# pca10056_sheet3_pin_map.net
KiCad netlist of a schematic drawn in Altium Designer
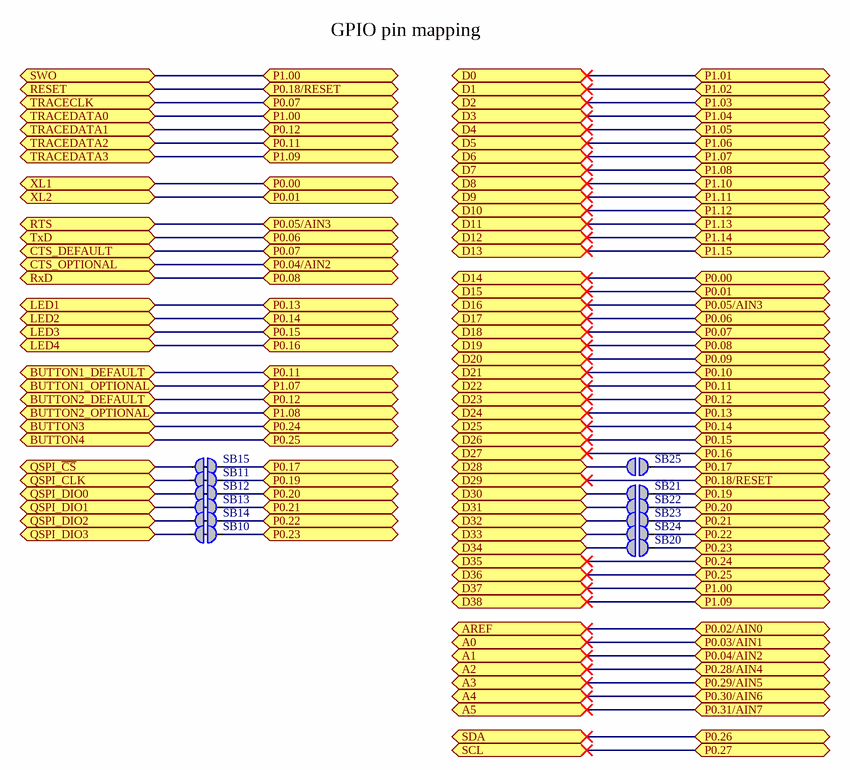
[diagram p0: pca10056_sheet3_pin_map.SchDoc]

(export (version "E")
  (design (tool "Eeschema 10.0.6"))
  (components
    (comp (ref "SB10")
      (value "Solderbridge")
      (footprint "Solderbridge_Shorted")
      (description "Shorted Solderbridge")
      (fields
        (field (name "PART NUMBER") "Solderbridge Shorted")
        (field (name "PUBLISHER") "Nordic Semiconductor")
      )
      (libsource (lib "Nordic Passive DB") (part "SOLDERBRIDGE_SHORTED"))
    )
    (comp (ref "SB11")
      (value "Solderbridge")
      (footprint "Solderbridge_Shorted")
      (description "Shorted Solderbridge")
      (fields
        (field (name "PART NUMBER") "Solderbridge Shorted")
        (field (name "PUBLISHER") "Nordic Semiconductor")
      )
      (libsource (lib "Nordic Passive DB") (part "SOLDERBRIDGE_SHORTED"))
    )
    (comp (ref "SB12")
      (value "Solderbridge")
      (footprint "Solderbridge_Shorted")
      (description "Shorted Solderbridge")
      (fields
        (field (name "PART NUMBER") "Solderbridge Shorted")
        (field (name "PUBLISHER") "Nordic Semiconductor")
      )
      (libsource (lib "Nordic Passive DB") (part "SOLDERBRIDGE_SHORTED"))
    )
    (comp (ref "SB13")
      (value "Solderbridge")
      (footprint "Solderbridge_Shorted")
      (description "Shorted Solderbridge")
      (fields
        (field (name "PART NUMBER") "Solderbridge Shorted")
        (field (name "PUBLISHER") "Nordic Semiconductor")
      )
      (libsource (lib "Nordic Passive DB") (part "SOLDERBRIDGE_SHORTED"))
    )
    (comp (ref "SB14")
      (value "Solderbridge")
      (footprint "Solderbridge_Shorted")
      (description "Shorted Solderbridge")
      (fields
        (field (name "PART NUMBER") "Solderbridge Shorted")
        (field (name "PUBLISHER") "Nordic Semiconductor")
      )
      (libsource (lib "Nordic Passive DB") (part "SOLDERBRIDGE_SHORTED"))
    )
    (comp (ref "SB15")
      (value "Solderbridge")
      (footprint "Solderbridge_Shorted")
      (description "Shorted Solderbridge")
      (fields
        (field (name "PART NUMBER") "Solderbridge Shorted")
        (field (name "PUBLISHER") "Nordic Semiconductor")
      )
      (libsource (lib "Nordic Passive DB") (part "SOLDERBRIDGE_SHORTED"))
    )
    (comp (ref "SB20")
      (value "Solderbridge")
      (footprint "Solderbridge")
      (fields (field (name "PUBLISHER") "Nordic Semiconductor"))
      (libsource (lib "Nordic Passive DB") (part "SOLDERBRIDGE"))
    )
    (comp (ref "SB21")
      (value "Solderbridge")
      (footprint "Solderbridge")
      (fields (field (name "PUBLISHER") "Nordic Semiconductor"))
      (libsource (lib "Nordic Passive DB") (part "SOLDERBRIDGE"))
    )
    (comp (ref "SB22")
      (value "Solderbridge")
      (footprint "Solderbridge")
      (fields (field (name "PUBLISHER") "Nordic Semiconductor"))
      (libsource (lib "Nordic Passive DB") (part "SOLDERBRIDGE"))
    )
    (comp (ref "SB23")
      (value "Solderbridge")
      (footprint "Solderbridge")
      (fields (field (name "PUBLISHER") "Nordic Semiconductor"))
      (libsource (lib "Nordic Passive DB") (part "SOLDERBRIDGE"))
    )
    (comp (ref "SB24")
      (value "Solderbridge")
      (footprint "Solderbridge")
      (fields (field (name "PUBLISHER") "Nordic Semiconductor"))
      (libsource (lib "Nordic Passive DB") (part "SOLDERBRIDGE"))
    )
    (comp (ref "SB25")
      (value "Solderbridge")
      (footprint "Solderbridge")
      (fields (field (name "PUBLISHER") "Nordic Semiconductor"))
      (libsource (lib "Nordic Passive DB") (part "SOLDERBRIDGE"))
    )
  )
  (nets
    (net (code "38") (name "/D28") (class "Default")
      (node (ref "SB25") (pin "2") (pinfunction "1_2") (pintype "passive"))
    )
    (net (code "40") (name "/D30") (class "Default")
      (node (ref "SB21") (pin "2") (pinfunction "1_2") (pintype "passive"))
    )
    (net (code "41") (name "/D31") (class "Default")
      (node (ref "SB22") (pin "2") (pinfunction "1_2") (pintype "passive"))
    )
    (net (code "42") (name "/D32") (class "Default")
      (node (ref "SB23") (pin "2") (pinfunction "1_2") (pintype "passive"))
    )
    (net (code "43") (name "/D33") (class "Default")
      (node (ref "SB24") (pin "2") (pinfunction "1_2") (pintype "passive"))
    )
    (net (code "44") (name "/D34") (class "Default")
      (node (ref "SB20") (pin "2") (pinfunction "1_2") (pintype "passive"))
    )
    (net (code "47") (name "/P0.17") (class "Default")
      (node (ref "SB15") (pin "1") (pinfunction "0_1") (pintype "passive"))
      (node (ref "SB25") (pin "1") (pinfunction "0_1") (pintype "passive"))
    )
    (net (code "48") (name "/P0.19") (class "Default")
      (node (ref "SB11") (pin "1") (pinfunction "0_1") (pintype "passive"))
      (node (ref "SB21") (pin "1") (pinfunction "0_1") (pintype "passive"))
    )
    (net (code "49") (name "/P0.20") (class "Default")
      (node (ref "SB12") (pin "1") (pinfunction "0_1") (pintype "passive"))
      (node (ref "SB22") (pin "1") (pinfunction "0_1") (pintype "passive"))
    )
    (net (code "50") (name "/P0.21") (class "Default")
      (node (ref "SB13") (pin "1") (pinfunction "0_1") (pintype "passive"))
      (node (ref "SB23") (pin "1") (pinfunction "0_1") (pintype "passive"))
    )
    (net (code "51") (name "/P0.22") (class "Default")
      (node (ref "SB14") (pin "1") (pinfunction "0_1") (pintype "passive"))
      (node (ref "SB24") (pin "1") (pinfunction "0_1") (pintype "passive"))
    )
    (net (code "52") (name "/P0.23") (class "Default")
      (node (ref "SB10") (pin "1") (pinfunction "0_1") (pintype "passive"))
      (node (ref "SB20") (pin "1") (pinfunction "0_1") (pintype "passive"))
    )
    (net (code "55") (name "/QSPI_CLK") (class "Default")
      (node (ref "SB11") (pin "2") (pinfunction "1_2") (pintype "passive"))
    )
    (net (code "56") (name "/QSPI_DIO0") (class "Default")
      (node (ref "SB12") (pin "2") (pinfunction "1_2") (pintype "passive"))
    )
    (net (code "57") (name "/QSPI_DIO1") (class "Default")
      (node (ref "SB13") (pin "2") (pinfunction "1_2") (pintype "passive"))
    )
    (net (code "58") (name "/QSPI_DIO2") (class "Default")
      (node (ref "SB14") (pin "2") (pinfunction "1_2") (pintype "passive"))
    )
    (net (code "59") (name "/QSPI_DIO3") (class "Default")
      (node (ref "SB10") (pin "2") (pinfunction "1_2") (pintype "passive"))
    )
    (net (code "60") (name "/QSPI_~{CS}") (class "Default")
      (node (ref "SB15") (pin "2") (pinfunction "1_2") (pintype "passive"))
    )
  )
)
